# BpodFSM_2Plus_r1_3.net
KiCad netlist of a schematic drawn in EAGLE
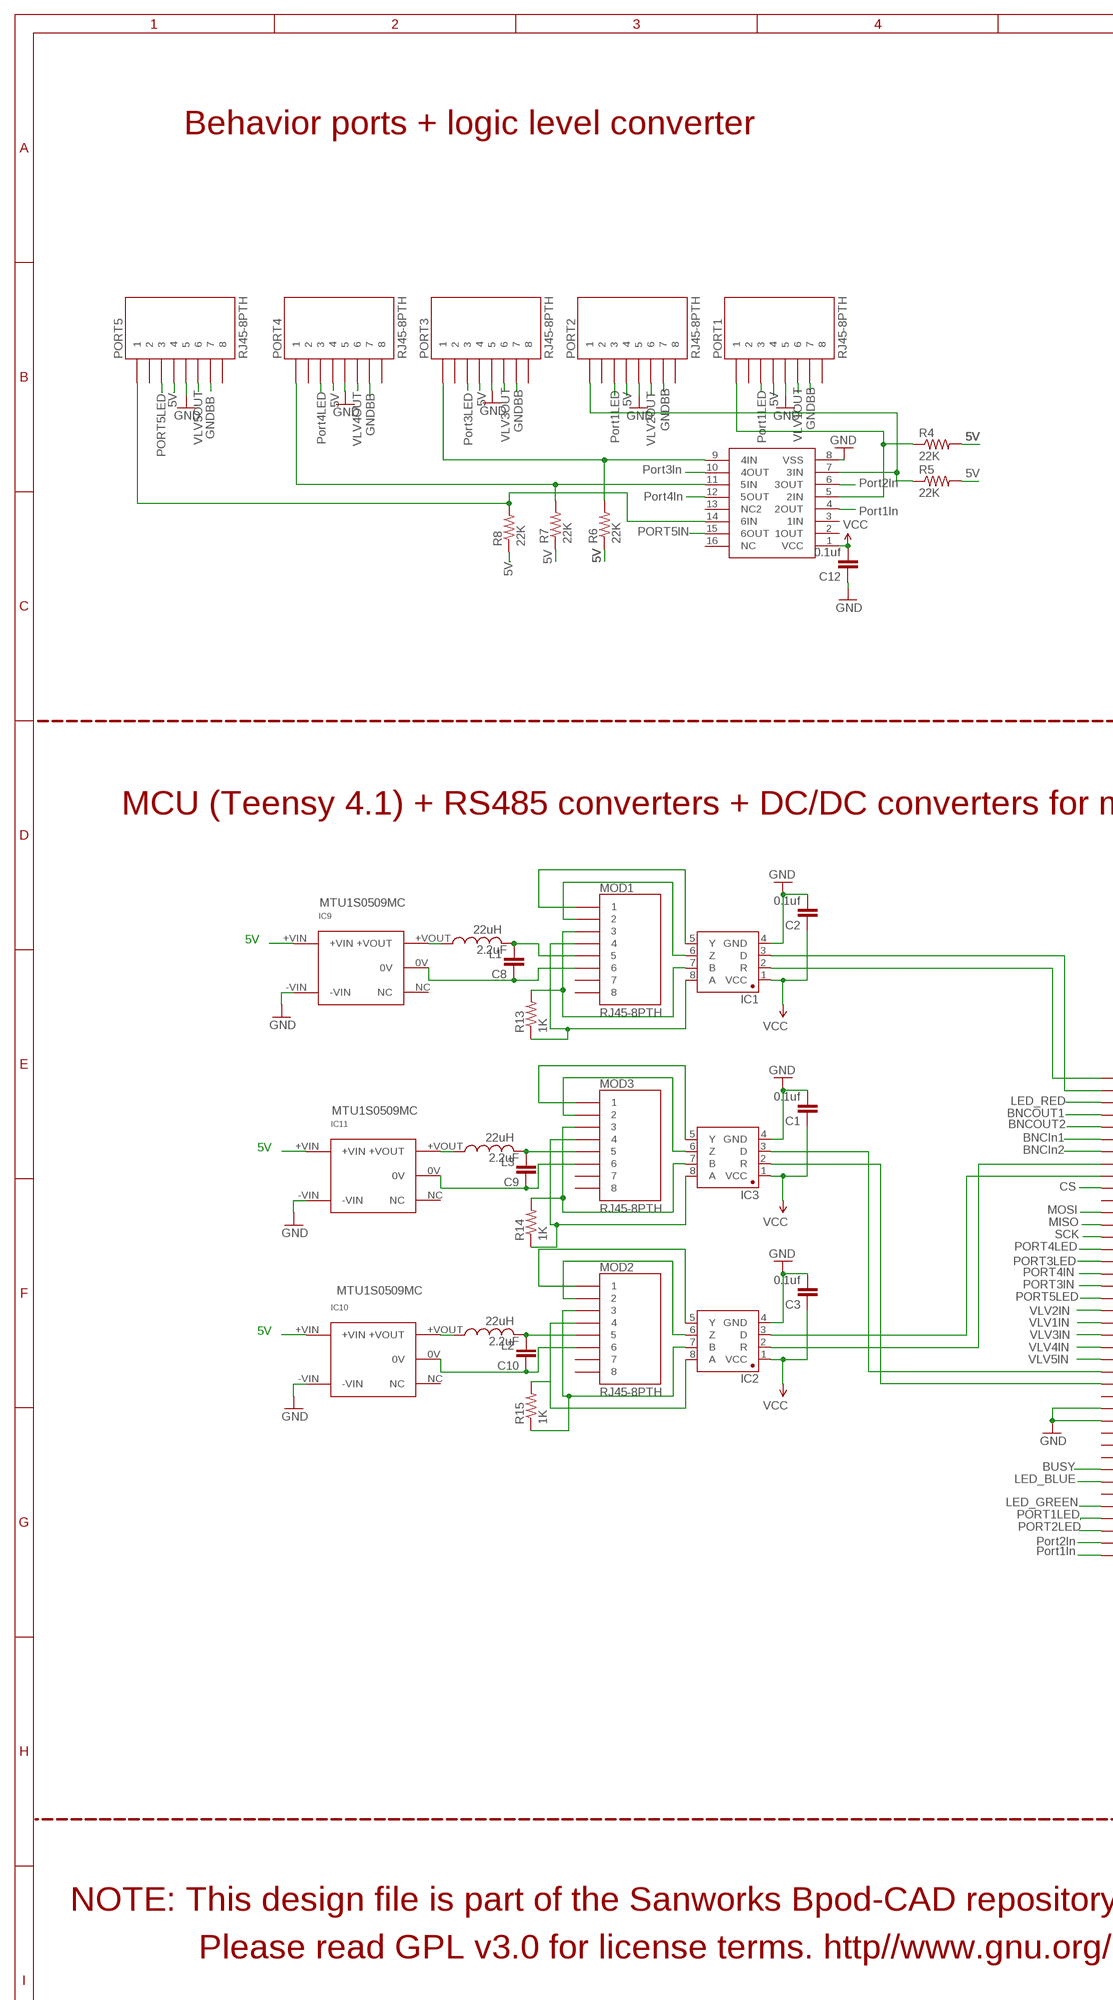
[diagram p0: schematic, sheet 1, part 1 of 2]
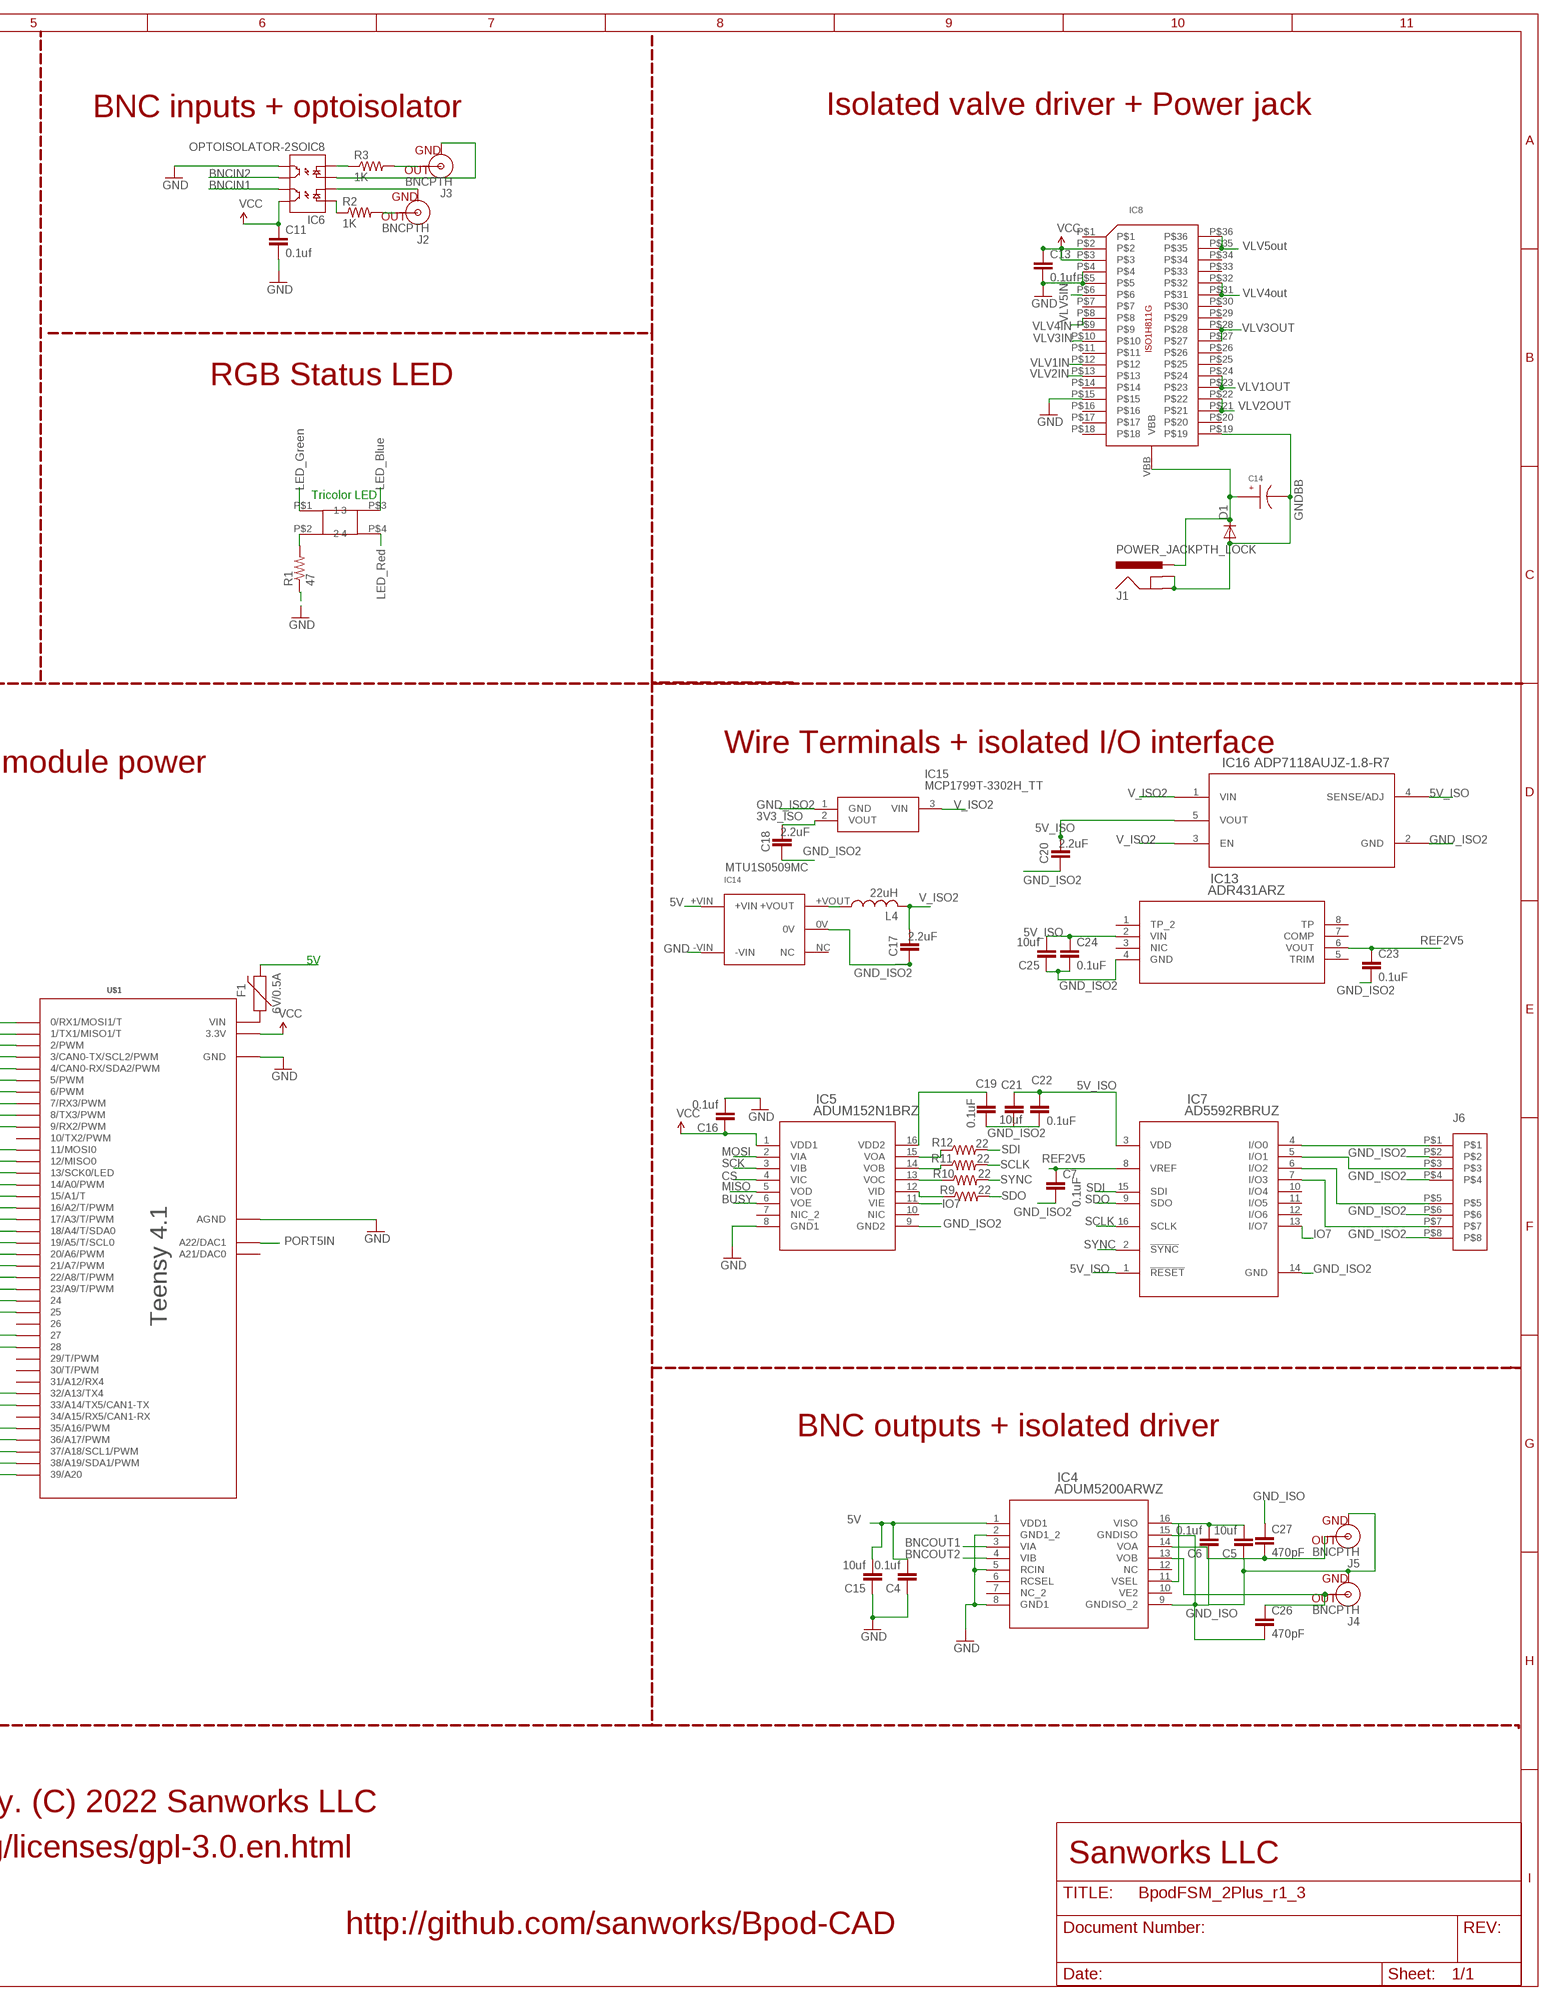
[diagram p1: schematic, sheet 1, part 2 of 2]

(export (version "E")
  (design (tool "Eeschema 10.0.6"))
  (components
    (comp (ref "C1")
      (value "0.1uf")
      (footprint "eagle-import:0805")
      (libsource (lib "eagle-import") (part "1.0UF-0805-25V-10%"))
    )
    (comp (ref "C2")
      (value "0.1uf")
      (footprint "eagle-import:0805")
      (libsource (lib "eagle-import") (part "1.0UF-0805-25V-10%"))
    )
    (comp (ref "C3")
      (value "0.1uf")
      (footprint "eagle-import:0805")
      (libsource (lib "eagle-import") (part "1.0UF-0805-25V-10%"))
    )
    (comp (ref "C4")
      (value "0.1uf")
      (footprint "eagle-import:0805")
      (libsource (lib "eagle-import") (part "1.0UF-0805-25V-10%"))
    )
    (comp (ref "C5")
      (value "10uf")
      (footprint "eagle-import:1206@1")
      (libsource (lib "eagle-import") (part "CAP1206"))
    )
    (comp (ref "C6")
      (value "0.1uf")
      (footprint "eagle-import:0805")
      (libsource (lib "eagle-import") (part "1.0UF-0805-25V-10%"))
    )
    (comp (ref "C7")
      (value "0.1uF")
      (footprint "eagle-import:0805")
      (libsource (lib "eagle-import") (part "1.0UF-0805-25V-10%"))
    )
    (comp (ref "C8")
      (value "2.2uF")
      (footprint "eagle-import:0805")
      (libsource (lib "eagle-import") (part "1.0UF-0805-25V-(+80/-20%)"))
    )
    (comp (ref "C9")
      (value "2.2uF")
      (footprint "eagle-import:0805")
      (libsource (lib "eagle-import") (part "1.0UF-0805-25V-(+80/-20%)"))
    )
    (comp (ref "C10")
      (value "2.2uF")
      (footprint "eagle-import:0805")
      (libsource (lib "eagle-import") (part "1.0UF-0805-25V-(+80/-20%)"))
    )
    (comp (ref "C11")
      (value "0.1uf")
      (footprint "eagle-import:0805")
      (libsource (lib "eagle-import") (part "1.0UF-0805-25V-10%"))
    )
    (comp (ref "C12")
      (value "0.1uf")
      (footprint "eagle-import:0805")
      (libsource (lib "eagle-import") (part "1.0UF-0805-25V-10%"))
    )
    (comp (ref "C13")
      (value "0.1uf")
      (footprint "eagle-import:0805")
      (libsource (lib "eagle-import") (part "1.0UF-0805-25V-10%"))
    )
    (comp (ref "C14")
      (value "EEE-FK1H100UR")
      (footprint "eagle-import:EEE-FK1H100UR")
      (libsource (lib "eagle-import") (part "EEE-FK1H100UR"))
    )
    (comp (ref "C15")
      (value "10uf")
      (footprint "eagle-import:1206@1")
      (libsource (lib "eagle-import") (part "CAP1206"))
    )
    (comp (ref "C16")
      (value "0.1uf")
      (footprint "eagle-import:0805")
      (libsource (lib "eagle-import") (part "1.0UF-0805-25V-10%"))
    )
    (comp (ref "C17")
      (value "2.2uF")
      (footprint "eagle-import:0805")
      (libsource (lib "eagle-import") (part "1.0UF-0805-25V-(+80/-20%)"))
    )
    (comp (ref "C18")
      (value "2.2uF")
      (footprint "eagle-import:0805")
      (libsource (lib "eagle-import") (part "1.0UF-0805-25V-(+80/-20%)"))
    )
    (comp (ref "C19")
      (value "0.1uF")
      (footprint "eagle-import:0805")
      (libsource (lib "eagle-import") (part "1.0UF-0805-25V-10%"))
    )
    (comp (ref "C20")
      (value "2.2uF")
      (footprint "eagle-import:0805")
      (libsource (lib "eagle-import") (part "1.0UF-0805-25V-(+80/-20%)"))
    )
    (comp (ref "C21")
      (value "10uf")
      (footprint "eagle-import:1206@1")
      (libsource (lib "eagle-import") (part "CAP1206"))
    )
    (comp (ref "C22")
      (value "0.1uF")
      (footprint "eagle-import:0805")
      (libsource (lib "eagle-import") (part "1.0UF-0805-25V-10%"))
    )
    (comp (ref "C23")
      (value "0.1uF")
      (footprint "eagle-import:0805")
      (libsource (lib "eagle-import") (part "1.0UF-0805-25V-10%"))
    )
    (comp (ref "C24")
      (value "0.1uF")
      (footprint "eagle-import:0805")
      (libsource (lib "eagle-import") (part "1.0UF-0805-25V-10%"))
    )
    (comp (ref "C25")
      (value "10uf")
      (footprint "eagle-import:1206@1")
      (libsource (lib "eagle-import") (part "CAP1206"))
    )
    (comp (ref "C26")
      (value "470pF")
      (footprint "eagle-import:0805")
      (libsource (lib "eagle-import") (part "1.0UF-0805-25V-10%"))
    )
    (comp (ref "C27")
      (value "470pF")
      (footprint "eagle-import:0805")
      (libsource (lib "eagle-import") (part "1.0UF-0805-25V-10%"))
    )
    (comp (ref "D1")
      (value "DIODE-DO214AA")
      (footprint "eagle-import:DO214AA")
      (libsource (lib "eagle-import") (part "DIODE-DO214AA"))
    )
    (comp (ref "F1")
      (value "6V/0.5A")
      (footprint "eagle-import:1206")
      (libsource (lib "eagle-import") (part "PPTC_HALF-AMP"))
    )
    (comp (ref "IC1")
      (value "SN65HVD31DR")
      (footprint "eagle-import:SO08")
      (libsource (lib "eagle-import") (part "SN65HVD31DR"))
    )
    (comp (ref "IC2")
      (value "SN65HVD31DR")
      (footprint "eagle-import:SO08")
      (libsource (lib "eagle-import") (part "SN65HVD31DR"))
    )
    (comp (ref "IC3")
      (value "SN65HVD31DR")
      (footprint "eagle-import:SO08")
      (libsource (lib "eagle-import") (part "SN65HVD31DR"))
    )
    (comp (ref "IC4")
      (value "ADUM5200ARWZ")
      (footprint "eagle-import:RW_16")
      (libsource (lib "eagle-import") (part "ADUM5200ARWZ"))
    )
    (comp (ref "IC5")
      (value "ADUM152N1BRZ")
      (footprint "eagle-import:R-16_ADI")
      (fields (field (name "COPYRIGHT") "Copyright (C) 2018 Accelerated Designs. All rights reserved"))
      (libsource (lib "eagle-import") (part "ADUM152N1BRZ"))
    )
    (comp (ref "IC6")
      (value "OPTOISOLATOR-2SOIC8")
      (footprint "eagle-import:SO08-2")
      (libsource (lib "eagle-import") (part "OPTOISOLATOR-2SOIC8"))
    )
    (comp (ref "IC7")
      (value "AD5592RBRUZ")
      (footprint "eagle-import:RU_16_ADI")
      (libsource (lib "eagle-import") (part "AD5592RBRUZ"))
    )
    (comp (ref "IC8")
      (value "ISO1H811G")
      (footprint "eagle-import:ISO1H811G")
      (libsource (lib "eagle-import") (part "ISO1H811G"))
    )
    (comp (ref "IC9")
      (value "9V")
      (footprint "eagle-import:MTU1D0505MC")
      (libsource (lib "eagle-import") (part "MTU1D0505MC"))
    )
    (comp (ref "IC10")
      (value "9V")
      (footprint "eagle-import:MTU1D0505MC")
      (libsource (lib "eagle-import") (part "MTU1D0505MC"))
    )
    (comp (ref "IC11")
      (value "9V")
      (footprint "eagle-import:MTU1D0505MC")
      (libsource (lib "eagle-import") (part "MTU1D0505MC"))
    )
    (comp (ref "IC12")
      (value "CD4050")
      (footprint "eagle-import:SO16")
      (libsource (lib "eagle-import") (part "CD4050"))
    )
    (comp (ref "IC13")
      (value "ADR431ARZ")
      (footprint "eagle-import:R_8_ADI")
      (libsource (lib "eagle-import") (part "ADR431ARZ"))
    )
    (comp (ref "IC14")
      (value "5V")
      (footprint "eagle-import:MTU1D0505MC")
      (libsource (lib "eagle-import") (part "MTU1D0505MC"))
    )
    (comp (ref "IC15")
      (value "MCP1799T-3302H_TT")
      (footprint "eagle-import:SOT95P237X112-3N")
      (fields
        (field (name "MANUFACTURER_PART_NUMBER") "MCP1799T-3302H/TT")
        (field (name "MOUSER_PART_NUMBER") "579-CP1799T-3302H/TT")
      )
      (libsource (lib "eagle-import") (part "MCP1799T-3302H_TT"))
    )
    (comp (ref "IC16")
      (value "ADP7118AUJZ-1.8-R7")
      (footprint "eagle-import:UJ_5")
      (libsource (lib "eagle-import") (part "ADP7118AUJZ-1.8-R7"))
    )
    (comp (ref "J1")
      (value "POWER_JACKPTH_LOCK")
      (footprint "eagle-import:POWER_JACK_PTH_LOCK")
      (libsource (lib "eagle-import") (part "POWER_JACKPTH_LOCK"))
    )
    (comp (ref "J2")
      (value "BNCPTH")
      (footprint "eagle-import:BNC")
      (libsource (lib "eagle-import") (part "BNCPTH"))
    )
    (comp (ref "J3")
      (value "BNCPTH")
      (footprint "eagle-import:BNC")
      (libsource (lib "eagle-import") (part "BNCPTH"))
    )
    (comp (ref "J4")
      (value "BNCPTH")
      (footprint "eagle-import:BNC")
      (libsource (lib "eagle-import") (part "BNCPTH"))
    )
    (comp (ref "J5")
      (value "BNCPTH")
      (footprint "eagle-import:BNC")
      (libsource (lib "eagle-import") (part "BNCPTH"))
    )
    (comp (ref "J6")
      (value "8POS_MOLEX_SOCKET")
      (footprint "eagle-import:8POS_MOLEX_SOCKET")
      (libsource (lib "eagle-import") (part "8POS_MOLEX_SOCKET"))
    )
    (comp (ref "L1")
      (value "22uH")
      (footprint "eagle-import:L3225M")
      (libsource (lib "eagle-import") (part "L-USL3225M"))
    )
    (comp (ref "L2")
      (value "22uH")
      (footprint "eagle-import:L3225M")
      (libsource (lib "eagle-import") (part "L-USL3225M"))
    )
    (comp (ref "L3")
      (value "22uH")
      (footprint "eagle-import:L3225M")
      (libsource (lib "eagle-import") (part "L-USL3225M"))
    )
    (comp (ref "L4")
      (value "22uH")
      (footprint "eagle-import:L3225M")
      (libsource (lib "eagle-import") (part "L-USL3225M"))
    )
    (comp (ref "MOD1")
      (value "RJ45-8PTH")
      (footprint "eagle-import:RJ45-8")
      (libsource (lib "eagle-import") (part "RJ45-8PTH"))
    )
    (comp (ref "MOD2")
      (value "RJ45-8PTH")
      (footprint "eagle-import:RJ45-8")
      (libsource (lib "eagle-import") (part "RJ45-8PTH"))
    )
    (comp (ref "MOD3")
      (value "RJ45-8PTH")
      (footprint "eagle-import:RJ45-8")
      (libsource (lib "eagle-import") (part "RJ45-8PTH"))
    )
    (comp (ref "PORT1")
      (value "RJ45-8PTH")
      (footprint "eagle-import:RJ45-8")
      (libsource (lib "eagle-import") (part "RJ45-8PTH"))
    )
    (comp (ref "PORT2")
      (value "RJ45-8PTH")
      (footprint "eagle-import:RJ45-8")
      (libsource (lib "eagle-import") (part "RJ45-8PTH"))
    )
    (comp (ref "PORT3")
      (value "RJ45-8PTH")
      (footprint "eagle-import:RJ45-8")
      (libsource (lib "eagle-import") (part "RJ45-8PTH"))
    )
    (comp (ref "PORT4")
      (value "RJ45-8PTH")
      (footprint "eagle-import:RJ45-8")
      (libsource (lib "eagle-import") (part "RJ45-8PTH"))
    )
    (comp (ref "PORT5")
      (value "RJ45-8PTH")
      (footprint "eagle-import:RJ45-8")
      (libsource (lib "eagle-import") (part "RJ45-8PTH"))
    )
    (comp (ref "R1")
      (value "47")
      (footprint "eagle-import:1206")
      (libsource (lib "eagle-import") (part "RESISTOR1206"))
    )
    (comp (ref "R2")
      (value "1K")
      (footprint "eagle-import:1206")
      (libsource (lib "eagle-import") (part "SparkFun-Resistors_RESISTOR1206"))
    )
    (comp (ref "R3")
      (value "1K")
      (footprint "eagle-import:1206")
      (libsource (lib "eagle-import") (part "SparkFun-Resistors_RESISTOR1206"))
    )
    (comp (ref "R4")
      (value "22K")
      (footprint "eagle-import:1206")
      (libsource (lib "eagle-import") (part "SparkFun-Resistors_RESISTOR1206"))
    )
    (comp (ref "R5")
      (value "22K")
      (footprint "eagle-import:1206")
      (libsource (lib "eagle-import") (part "SparkFun-Resistors_RESISTOR1206"))
    )
    (comp (ref "R6")
      (value "22K")
      (footprint "eagle-import:1206")
      (libsource (lib "eagle-import") (part "SparkFun-Resistors_RESISTOR1206"))
    )
    (comp (ref "R7")
      (value "22K")
      (footprint "eagle-import:1206")
      (libsource (lib "eagle-import") (part "SparkFun-Resistors_RESISTOR1206"))
    )
    (comp (ref "R8")
      (value "22K")
      (footprint "eagle-import:1206")
      (libsource (lib "eagle-import") (part "SparkFun-Resistors_RESISTOR1206"))
    )
    (comp (ref "R9")
      (value "22")
      (footprint "eagle-import:R0805")
      (libsource (lib "eagle-import") (part "R-US_R0805"))
    )
    (comp (ref "R10")
      (value "22")
      (footprint "eagle-import:R0805")
      (libsource (lib "eagle-import") (part "R-US_R0805"))
    )
    (comp (ref "R11")
      (value "22")
      (footprint "eagle-import:R0805")
      (libsource (lib "eagle-import") (part "R-US_R0805"))
    )
    (comp (ref "R12")
      (value "22")
      (footprint "eagle-import:R0805")
      (libsource (lib "eagle-import") (part "R-US_R0805"))
    )
    (comp (ref "R13")
      (value "1K")
      (footprint "eagle-import:1206")
      (libsource (lib "eagle-import") (part "SparkFun-Resistors_RESISTOR1206"))
    )
    (comp (ref "R14")
      (value "1K")
      (footprint "eagle-import:1206")
      (libsource (lib "eagle-import") (part "SparkFun-Resistors_RESISTOR1206"))
    )
    (comp (ref "R15")
      (value "1K")
      (footprint "eagle-import:1206")
      (libsource (lib "eagle-import") (part "SparkFun-Resistors_RESISTOR1206"))
    )
    (comp (ref "U$1")
      (value "TEENSY_3.6_DIL")
      (footprint "eagle-import:TEENSY_3.6_DIL")
      (libsource (lib "eagle-import") (part "TEENSY_3.6_DIL"))
    )
    (comp (ref "U$8")
      (value "SQUARE_TRICOLOR_LED")
      (footprint "eagle-import:SQUARE_TRICOLOR_LED")
      (libsource (lib "eagle-import") (part "SQUARE_TRICOLOR_LED"))
    )
  )
  (nets
    (net (code "1") (name "/3V3_ISO") (class "Default")
      (node (ref "C18") (pin "2") (pinfunction "2_2") (pintype "passive"))
      (node (ref "C19") (pin "1") (pinfunction "1_1") (pintype "passive"))
      (node (ref "IC15") (pin "2") (pinfunction "VOUT_2") (pintype "bidirectional"))
      (node (ref "IC5") (pin "16") (pinfunction "VDD2_16") (pintype "power_in"))
    )
    (net (code "2") (name "/5V") (class "Default")
      (node (ref "C15") (pin "2") (pinfunction "2_2") (pintype "passive"))
      (node (ref "C4") (pin "2") (pinfunction "2_2") (pintype "passive"))
      (node (ref "F1") (pin "2") (pinfunction "2_2") (pintype "bidirectional"))
      (node (ref "IC10") (pin "+VIN") (pinfunction "+VIN_+VIN") (pintype "bidirectional"))
      (node (ref "IC11") (pin "+VIN") (pinfunction "+VIN_+VIN") (pintype "bidirectional"))
      (node (ref "IC14") (pin "+VIN") (pinfunction "+VIN_+VIN") (pintype "bidirectional"))
      (node (ref "IC4") (pin "1") (pinfunction "VDD1_1") (pintype "passive"))
      (node (ref "IC9") (pin "+VIN") (pinfunction "+VIN_+VIN") (pintype "bidirectional"))
      (node (ref "PORT1") (pin "4") (pinfunction "4_4") (pintype "bidirectional"))
      (node (ref "PORT2") (pin "4") (pinfunction "4_4") (pintype "bidirectional"))
      (node (ref "PORT3") (pin "4") (pinfunction "4_4") (pintype "bidirectional"))
      (node (ref "PORT4") (pin "4") (pinfunction "4_4") (pintype "bidirectional"))
      (node (ref "PORT5") (pin "4") (pinfunction "4_4") (pintype "bidirectional"))
      (node (ref "R4") (pin "2") (pinfunction "2_2") (pintype "passive"))
      (node (ref "R5") (pin "2") (pinfunction "2_2") (pintype "passive"))
      (node (ref "R6") (pin "1") (pinfunction "1_1") (pintype "passive"))
      (node (ref "R7") (pin "1") (pinfunction "1_1") (pintype "passive"))
      (node (ref "R8") (pin "1") (pinfunction "1_1") (pintype "passive"))
    )
    (net (code "3") (name "/5V_ISO") (class "Default")
      (node (ref "C20") (pin "2") (pinfunction "2_2") (pintype "passive"))
      (node (ref "C21") (pin "2") (pinfunction "2_2") (pintype "passive"))
      (node (ref "C22") (pin "1") (pinfunction "1_1") (pintype "passive"))
      (node (ref "C24") (pin "1") (pinfunction "1_1") (pintype "passive"))
      (node (ref "C25") (pin "2") (pinfunction "2_2") (pintype "passive"))
      (node (ref "IC13") (pin "2") (pinfunction "VIN_2") (pintype "input"))
      (node (ref "IC16") (pin "4") (pinfunction "SENSE/ADJ_4") (pintype "passive"))
      (node (ref "IC16") (pin "5") (pinfunction "VOUT_5") (pintype "passive"))
      (node (ref "IC7") (pin "1") (pinfunction "~{RESET}_1") (pintype "passive"))
      (node (ref "IC7") (pin "3") (pinfunction "VDD_3") (pintype "passive"))
    )
    (net (code "4") (name "/BNCIN1") (class "Default")
      (node (ref "IC6") (pin "7") (pinfunction "EM1_7") (pintype "bidirectional"))
      (node (ref "U$1") (pin "6") (pinfunction "6/PWM_6") (pintype "bidirectional"))
    )
    (net (code "5") (name "/BNCIN2") (class "Default")
      (node (ref "IC6") (pin "6") (pinfunction "CL2_6") (pintype "bidirectional"))
      (node (ref "U$1") (pin "5") (pinfunction "5/PWM_5") (pintype "bidirectional"))
    )
    (net (code "6") (name "/BNCOUT1") (class "Default")
      (node (ref "IC4") (pin "3") (pinfunction "VIA_3") (pintype "passive"))
      (node (ref "U$1") (pin "3") (pinfunction "3/CAN0-TX/SCL2/PWM_3") (pintype "bidirectional"))
    )
    (net (code "7") (name "/BNCOUT2") (class "Default")
      (node (ref "IC4") (pin "4") (pinfunction "VIB_4") (pintype "passive"))
      (node (ref "U$1") (pin "4") (pinfunction "4/CAN0-RX/SDA2/PWM_4") (pintype "bidirectional"))
    )
    (net (code "8") (name "/BUSY") (class "Default")
      (node (ref "IC5") (pin "6") (pinfunction "VOE_6") (pintype "output"))
      (node (ref "U$1") (pin "32/A13") (pinfunction "32/A13/TX4_32/A13") (pintype "bidirectional"))
    )
    (net (code "9") (name "/CS") (class "Default")
      (node (ref "IC5") (pin "4") (pinfunction "VIC_4") (pintype "input"))
      (node (ref "U$1") (pin "9") (pinfunction "9/RX2/PWM_9") (pintype "bidirectional"))
    )
    (net (code "10") (name "/GNDBB") (class "Default")
      (node (ref "C14") (pin "CATHODE") (pinfunction "CATHODE_CATHODE") (pintype "bidirectional"))
      (node (ref "D1") (pin "A") (pinfunction "A_A") (pintype "passive"))
      (node (ref "IC8") (pin "P$19") (pinfunction "P$19_P$19") (pintype "bidirectional"))
      (node (ref "J1") (pin "GND") (pinfunction "GND_GND") (pintype "bidirectional"))
      (node (ref "J1") (pin "GNDBREAK") (pinfunction "GNDBREAK_GNDBREAK") (pintype "bidirectional"))
      (node (ref "PORT1") (pin "7") (pinfunction "7_7") (pintype "bidirectional"))
      (node (ref "PORT2") (pin "7") (pinfunction "7_7") (pintype "bidirectional"))
      (node (ref "PORT3") (pin "7") (pinfunction "7_7") (pintype "bidirectional"))
      (node (ref "PORT4") (pin "7") (pinfunction "7_7") (pintype "bidirectional"))
      (node (ref "PORT5") (pin "7") (pinfunction "7_7") (pintype "bidirectional"))
    )
    (net (code "11") (name "/GND_ISO") (class "Default")
      (node (ref "C26") (pin "2") (pinfunction "2_2") (pintype "passive"))
      (node (ref "C27") (pin "1") (pinfunction "1_1") (pintype "passive"))
      (node (ref "C5") (pin "1") (pinfunction "1_1") (pintype "passive"))
      (node (ref "C6") (pin "1") (pinfunction "1_1") (pintype "passive"))
      (node (ref "IC4") (pin "15") (pinfunction "GNDISO_15") (pintype "passive"))
      (node (ref "IC4") (pin "9") (pinfunction "GNDISO_2_9") (pintype "passive"))
      (node (ref "J4") (pin "GND") (pinfunction "GND_GND") (pintype "bidirectional"))
      (node (ref "J5") (pin "GND") (pinfunction "GND_GND") (pintype "bidirectional"))
    )
    (net (code "12") (name "/GND_ISO2") (class "Default")
      (node (ref "C17") (pin "1") (pinfunction "1_1") (pintype "passive"))
      (node (ref "C18") (pin "1") (pinfunction "1_1") (pintype "passive"))
      (node (ref "C19") (pin "2") (pinfunction "2_2") (pintype "passive"))
      (node (ref "C20") (pin "1") (pinfunction "1_1") (pintype "passive"))
      (node (ref "C21") (pin "1") (pinfunction "1_1") (pintype "passive"))
      (node (ref "C22") (pin "2") (pinfunction "2_2") (pintype "passive"))
      (node (ref "C23") (pin "2") (pinfunction "2_2") (pintype "passive"))
      (node (ref "C24") (pin "2") (pinfunction "2_2") (pintype "passive"))
      (node (ref "C25") (pin "1") (pinfunction "1_1") (pintype "passive"))
      (node (ref "C7") (pin "2") (pinfunction "2_2") (pintype "passive"))
      (node (ref "IC13") (pin "4") (pinfunction "GND_4") (pintype "power_in"))
      (node (ref "IC14") (pin "0V") (pinfunction "0V_0V") (pintype "bidirectional"))
      (node (ref "IC15") (pin "1") (pinfunction "GND_1") (pintype "bidirectional"))
      (node (ref "IC16") (pin "2") (pinfunction "GND_2") (pintype "passive"))
      (node (ref "IC5") (pin "9") (pinfunction "GND2_9") (pintype "passive"))
      (node (ref "IC7") (pin "14") (pinfunction "GND_14") (pintype "passive"))
      (node (ref "J6") (pin "P$2") (pinfunction "P$2_P$2") (pintype "bidirectional"))
      (node (ref "J6") (pin "P$4") (pinfunction "P$4_P$4") (pintype "bidirectional"))
      (node (ref "J6") (pin "P$6") (pinfunction "P$6_P$6") (pintype "bidirectional"))
      (node (ref "J6") (pin "P$8") (pinfunction "P$8_P$8") (pintype "bidirectional"))
    )
    (net (code "13") (name "/IO7") (class "Default")
      (node (ref "IC5") (pin "11") (pinfunction "VIE_11") (pintype "input"))
      (node (ref "IC7") (pin "13") (pinfunction "I/O7_13") (pintype "passive"))
    )
    (net (code "14") (name "/LED_BLUE") (class "Default")
      (node (ref "U$1") (pin "33/A14") (pinfunction "33/A14/TX5/CAN1-TX_33/A14") (pintype "bidirectional"))
      (node (ref "U$8") (pin "P$3") (pinfunction "3_P$3") (pintype "bidirectional"))
    )
    (net (code "15") (name "/LED_GREEN") (class "Default")
      (node (ref "U$1") (pin "35/A16") (pinfunction "35/A16/PWM_35/A16") (pintype "bidirectional"))
      (node (ref "U$8") (pin "P$1") (pinfunction "1_P$1") (pintype "bidirectional"))
    )
    (net (code "16") (name "/LED_RED") (class "Default")
      (node (ref "U$1") (pin "2") (pinfunction "2/PWM_2") (pintype "bidirectional"))
      (node (ref "U$8") (pin "P$4") (pinfunction "4_P$4") (pintype "bidirectional"))
    )
    (net (code "17") (name "/MISO") (class "Default")
      (node (ref "IC5") (pin "5") (pinfunction "VOD_5") (pintype "output"))
      (node (ref "U$1") (pin "12") (pinfunction "12/MISO0_12") (pintype "bidirectional"))
    )
    (net (code "18") (name "/MOSI") (class "Default")
      (node (ref "IC5") (pin "2") (pinfunction "VIA_2") (pintype "input"))
      (node (ref "U$1") (pin "11") (pinfunction "11/MOSI0_11") (pintype "bidirectional"))
    )
    (net (code "19") (name "/PORT1IN") (class "Default")
      (node (ref "IC12") (pin "4") (pinfunction "2OUT_4") (pintype "bidirectional"))
      (node (ref "U$1") (pin "39/A20") (pinfunction "39/A20_39/A20") (pintype "bidirectional"))
    )
    (net (code "20") (name "/PORT1LED") (class "Default")
      (node (ref "PORT1") (pin "3") (pinfunction "3_3") (pintype "bidirectional"))
      (node (ref "U$1") (pin "36/A17") (pinfunction "36/A17/PWM_36/A17") (pintype "bidirectional"))
    )
    (net (code "21") (name "/PORT2IN") (class "Default")
      (node (ref "IC12") (pin "6") (pinfunction "3OUT_6") (pintype "bidirectional"))
      (node (ref "U$1") (pin "38/A19") (pinfunction "38/A19/SDA1/PWM_38/A19") (pintype "bidirectional"))
    )
    (net (code "22") (name "/PORT2LED") (class "Default")
      (node (ref "PORT2") (pin "3") (pinfunction "3_3") (pintype "bidirectional"))
      (node (ref "U$1") (pin "37/A18") (pinfunction "37/A18/SCL1/PWM_37/A18") (pintype "bidirectional"))
    )
    (net (code "23") (name "/PORT3IN") (class "Default")
      (node (ref "IC12") (pin "10") (pinfunction "4OUT_10") (pintype "bidirectional"))
      (node (ref "U$1") (pin "17/A3") (pinfunction "17/A3/T/PWM_17/A3") (pintype "bidirectional"))
    )
    (net (code "24") (name "/PORT3LED") (class "Default")
      (node (ref "PORT3") (pin "3") (pinfunction "3_3") (pintype "bidirectional"))
      (node (ref "U$1") (pin "15/A1") (pinfunction "15/A1/T_15/A1") (pintype "bidirectional"))
    )
    (net (code "25") (name "/PORT4IN") (class "Default")
      (node (ref "IC12") (pin "12") (pinfunction "5OUT_12") (pintype "bidirectional"))
      (node (ref "U$1") (pin "16/A2") (pinfunction "16/A2/T/PWM_16/A2") (pintype "bidirectional"))
    )
    (net (code "26") (name "/PORT4LED") (class "Default")
      (node (ref "PORT4") (pin "3") (pinfunction "3_3") (pintype "bidirectional"))
      (node (ref "U$1") (pin "14/A0") (pinfunction "14/A0/PWM_14/A0") (pintype "bidirectional"))
    )
    (net (code "27") (name "/PORT5IN") (class "Default")
      (node (ref "IC12") (pin "15") (pinfunction "6OUT_15") (pintype "bidirectional"))
      (node (ref "U$1") (pin "A22") (pinfunction "A22/DAC1_A22") (pintype "bidirectional"))
    )
    (net (code "28") (name "/PORT5LED") (class "Default")
      (node (ref "PORT5") (pin "3") (pinfunction "3_3") (pintype "bidirectional"))
      (node (ref "U$1") (pin "18/A4") (pinfunction "18/A4/T/SDA0_18/A4") (pintype "bidirectional"))
    )
    (net (code "29") (name "/REF2V5") (class "Default")
      (node (ref "C23") (pin "1") (pinfunction "1_1") (pintype "passive"))
      (node (ref "C7") (pin "1") (pinfunction "1_1") (pintype "passive"))
      (node (ref "IC13") (pin "6") (pinfunction "VOUT_6") (pintype "output"))
      (node (ref "IC7") (pin "8") (pinfunction "VREF_8") (pintype "passive"))
    )
    (net (code "30") (name "/SCK") (class "Default")
      (node (ref "IC5") (pin "3") (pinfunction "VIB_3") (pintype "input"))
      (node (ref "U$1") (pin "13") (pinfunction "13/SCK0/LED_13") (pintype "bidirectional"))
    )
    (net (code "31") (name "/SCLK") (class "Default")
      (node (ref "IC7") (pin "16") (pinfunction "SCLK_16") (pintype "passive"))
      (node (ref "R11") (pin "2") (pinfunction "2_2") (pintype "passive"))
    )
    (net (code "32") (name "/SDI") (class "Default")
      (node (ref "IC7") (pin "15") (pinfunction "SDI_15") (pintype "passive"))
      (node (ref "R12") (pin "2") (pinfunction "2_2") (pintype "passive"))
    )
    (net (code "33") (name "/SDO") (class "Default")
      (node (ref "IC7") (pin "9") (pinfunction "SDO_9") (pintype "passive"))
      (node (ref "R9") (pin "2") (pinfunction "2_2") (pintype "passive"))
    )
    (net (code "34") (name "/SYNC") (class "Default")
      (node (ref "IC7") (pin "2") (pinfunction "~{SYNC}_2") (pintype "passive"))
      (node (ref "R10") (pin "2") (pinfunction "2_2") (pintype "passive"))
    )
    (net (code "35") (name "/VLV1IN") (class "Default")
      (node (ref "IC8") (pin "P$12") (pinfunction "P$12_P$12") (pintype "bidirectional"))
      (node (ref "U$1") (pin "20/A6") (pinfunction "20/A6/PWM_20/A6") (pintype "bidirectional"))
    )
    (net (code "36") (name "/VLV1OUT") (class "Default")
      (node (ref "IC8") (pin "P$23") (pinfunction "P$23_P$23") (pintype "bidirectional"))
      (node (ref "IC8") (pin "P$24") (pinfunction "P$24_P$24") (pintype "bidirectional"))
      (node (ref "PORT1") (pin "6") (pinfunction "6_6") (pintype "bidirectional"))
    )
    (net (code "37") (name "/VLV2IN") (class "Default")
      (node (ref "IC8") (pin "P$13") (pinfunction "P$13_P$13") (pintype "bidirectional"))
      (node (ref "U$1") (pin "19/A5") (pinfunction "19/A5/T/SCL0_19/A5") (pintype "bidirectional"))
    )
    (net (code "38") (name "/VLV2OUT") (class "Default")
      (node (ref "IC8") (pin "P$21") (pinfunction "P$21_P$21") (pintype "bidirectional"))
      (node (ref "IC8") (pin "P$22") (pinfunction "P$22_P$22") (pintype "bidirectional"))
      (node (ref "PORT2") (pin "6") (pinfunction "6_6") (pintype "bidirectional"))
    )
    (net (code "39") (name "/VLV3IN") (class "Default")
      (node (ref "IC8") (pin "P$10") (pinfunction "P$10_P$10") (pintype "bidirectional"))
      (node (ref "U$1") (pin "21/A7") (pinfunction "21/A7/PWM_21/A7") (pintype "bidirectional"))
    )
    (net (code "40") (name "/VLV3OUT") (class "Default")
      (node (ref "IC8") (pin "P$27") (pinfunction "P$27_P$27") (pintype "bidirectional"))
      (node (ref "IC8") (pin "P$28") (pinfunction "P$28_P$28") (pintype "bidirectional"))
      (node (ref "PORT3") (pin "6") (pinfunction "6_6") (pintype "bidirectional"))
    )
    (net (code "41") (name "/VLV4IN") (class "Default")
      (node (ref "IC8") (pin "P$8") (pinfunction "P$8_P$8") (pintype "bidirectional"))
      (node (ref "U$1") (pin "22/A8") (pinfunction "22/A8/T/PWM_22/A8") (pintype "bidirectional"))
    )
    (net (code "42") (name "/VLV4OUT") (class "Default")
      (node (ref "IC8") (pin "P$31") (pinfunction "P$31_P$31") (pintype "bidirectional"))
      (node (ref "IC8") (pin "P$32") (pinfunction "P$32_P$32") (pintype "bidirectional"))
      (node (ref "PORT4") (pin "6") (pinfunction "6_6") (pintype "bidirectional"))
    )
    (net (code "43") (name "/VLV5IN") (class "Default")
      (node (ref "IC8") (pin "P$6") (pinfunction "P$6_P$6") (pintype "bidirectional"))
      (node (ref "U$1") (pin "23/A9") (pinfunction "23/A9/T/PWM_23/A9") (pintype "bidirectional"))
    )
    (net (code "44") (name "/VLV5OUT") (class "Default")
      (node (ref "IC8") (pin "P$35") (pinfunction "P$35_P$35") (pintype "bidirectional"))
      (node (ref "IC8") (pin "P$36") (pinfunction "P$36_P$36") (pintype "bidirectional"))
      (node (ref "PORT5") (pin "6") (pinfunction "6_6") (pintype "bidirectional"))
    )
    (net (code "45") (name "/V_ISO2") (class "Default")
      (node (ref "C17") (pin "2") (pinfunction "2_2") (pintype "passive"))
      (node (ref "IC15") (pin "3") (pinfunction "VIN_3") (pintype "bidirectional"))
      (node (ref "IC16") (pin "1") (pinfunction "VIN_1") (pintype "passive"))
      (node (ref "IC16") (pin "3") (pinfunction "EN_3") (pintype "passive"))
      (node (ref "L4") (pin "2") (pinfunction "2_2") (pintype "passive"))
    )
    (net (code "46") (name "GND") (class "Default")
      (node (ref "C1") (pin "2") (pinfunction "2_2") (pintype "passive"))
      (node (ref "C11") (pin "2") (pinfunction "2_2") (pintype "passive"))
      (node (ref "C12") (pin "1") (pinfunction "1_1") (pintype "passive"))
      (node (ref "C13") (pin "2") (pinfunction "2_2") (pintype "passive"))
      (node (ref "C15") (pin "1") (pinfunction "1_1") (pintype "passive"))
      (node (ref "C16") (pin "2") (pinfunction "2_2") (pintype "passive"))
      (node (ref "C2") (pin "2") (pinfunction "2_2") (pintype "passive"))
      (node (ref "C3") (pin "2") (pinfunction "2_2") (pintype "passive"))
      (node (ref "C4") (pin "1") (pinfunction "1_1") (pintype "passive"))
      (node (ref "IC1") (pin "4") (pinfunction "GND_4") (pintype "bidirectional"))
      (node (ref "IC10") (pin "-VIN") (pinfunction "-VIN_-VIN") (pintype "bidirectional"))
      (node (ref "IC11") (pin "-VIN") (pinfunction "-VIN_-VIN") (pintype "bidirectional"))
      (node (ref "IC12") (pin "8") (pinfunction "VSS_8") (pintype "bidirectional"))
      (node (ref "IC14") (pin "-VIN") (pinfunction "-VIN_-VIN") (pintype "bidirectional"))
      (node (ref "IC2") (pin "4") (pinfunction "GND_4") (pintype "bidirectional"))
      (node (ref "IC3") (pin "4") (pinfunction "GND_4") (pintype "bidirectional"))
      (node (ref "IC4") (pin "2") (pinfunction "GND1_2_2") (pintype "passive"))
      (node (ref "IC4") (pin "5") (pinfunction "RCIN_5") (pintype "passive"))
      (node (ref "IC4") (pin "8") (pinfunction "GND1_8") (pintype "passive"))
      (node (ref "IC5") (pin "8") (pinfunction "GND1_8") (pintype "passive"))
      (node (ref "IC6") (pin "5") (pinfunction "EM2_5") (pintype "bidirectional"))
      (node (ref "IC8") (pin "P$15") (pinfunction "P$15_P$15") (pintype "bidirectional"))
      (node (ref "IC8") (pin "P$4") (pinfunction "P$4_P$4") (pintype "bidirectional"))
      (node (ref "IC8") (pin "P$5") (pinfunction "P$5_P$5") (pintype "bidirectional"))
      (node (ref "IC9") (pin "-VIN") (pinfunction "-VIN_-VIN") (pintype "bidirectional"))
      (node (ref "PORT1") (pin "5") (pinfunction "5_5") (pintype "bidirectional"))
      (node (ref "PORT2") (pin "5") (pinfunction "5_5") (pintype "bidirectional"))
      (node (ref "PORT3") (pin "5") (pinfunction "5_5") (pintype "bidirectional"))
      (node (ref "PORT4") (pin "5") (pinfunction "5_5") (pintype "bidirectional"))
      (node (ref "PORT5") (pin "5") (pinfunction "5_5") (pintype "bidirectional"))
      (node (ref "R1") (pin "1") (pinfunction "1_1") (pintype "passive"))
      (node (ref "U$1") (pin "27") (pinfunction "27_27") (pintype "bidirectional"))
      (node (ref "U$1") (pin "28") (pinfunction "28_28") (pintype "bidirectional"))
      (node (ref "U$1") (pin "AGND") (pinfunction "AGND_AGND") (pintype "power_in"))
      (node (ref "U$1") (pin "GND") (pinfunction "GND_GND") (pintype "power_in"))
      (node (ref "U$1") (pin "GND1") (pinfunction "GND_GND1") (pintype "power_in"))
    )
    (net (code "47") (name "Net-(C8-Pad1)") (class "Default")
      (node (ref "C8") (pin "1") (pinfunction "1_1") (pintype "passive"))
      (node (ref "IC9") (pin "0V") (pinfunction "0V_0V") (pintype "bidirectional"))
      (node (ref "MOD1") (pin "6") (pinfunction "6_6") (pintype "bidirectional"))
    )
    (net (code "48") (name "Net-(C8-Pad2)") (class "Default")
      (node (ref "C8") (pin "2") (pinfunction "2_2") (pintype "passive"))
      (node (ref "L1") (pin "2") (pinfunction "2_2") (pintype "passive"))
      (node (ref "MOD1") (pin "5") (pinfunction "5_5") (pintype "bidirectional"))
    )
    (net (code "49") (name "Net-(C9-Pad1)") (class "Default")
      (node (ref "C9") (pin "1") (pinfunction "1_1") (pintype "passive"))
      (node (ref "IC11") (pin "0V") (pinfunction "0V_0V") (pintype "bidirectional"))
      (node (ref "MOD3") (pin "6") (pinfunction "6_6") (pintype "bidirectional"))
    )
    (net (code "50") (name "Net-(C9-Pad2)") (class "Default")
      (node (ref "C9") (pin "2") (pinfunction "2_2") (pintype "passive"))
      (node (ref "L3") (pin "2") (pinfunction "2_2") (pintype "passive"))
      (node (ref "MOD3") (pin "5") (pinfunction "5_5") (pintype "bidirectional"))
    )
    (net (code "51") (name "Net-(C10-Pad1)") (class "Default")
      (node (ref "C10") (pin "1") (pinfunction "1_1") (pintype "passive"))
      (node (ref "IC10") (pin "0V") (pinfunction "0V_0V") (pintype "bidirectional"))
      (node (ref "MOD2") (pin "6") (pinfunction "6_6") (pintype "bidirectional"))
    )
    (net (code "52") (name "Net-(C10-Pad2)") (class "Default")
      (node (ref "C10") (pin "2") (pinfunction "2_2") (pintype "passive"))
      (node (ref "L2") (pin "2") (pinfunction "2_2") (pintype "passive"))
      (node (ref "MOD2") (pin "5") (pinfunction "5_5") (pintype "bidirectional"))
    )
    (net (code "53") (name "Net-(C14-PadANODE)") (class "Default")
      (node (ref "C14") (pin "ANODE") (pinfunction "ANODE_ANODE") (pintype "bidirectional"))
      (node (ref "D1") (pin "C") (pinfunction "C_C") (pintype "passive"))
      (node (ref "IC8") (pin "VBB") (pinfunction "VBB_VBB") (pintype "bidirectional"))
      (node (ref "J1") (pin "PWR") (pinfunction "PWR_PWR") (pintype "bidirectional"))
    )
    (net (code "54") (name "Net-(F1-Pad1)") (class "Default")
      (node (ref "F1") (pin "1") (pinfunction "1_1") (pintype "bidirectional"))
      (node (ref "U$1") (pin "VIN") (pinfunction "VIN_VIN") (pintype "power_in"))
    )
    (net (code "55") (name "Net-(IC1-A)") (class "Default")
      (node (ref "IC1") (pin "8") (pinfunction "A_8") (pintype "bidirectional"))
      (node (ref "MOD1") (pin "4") (pinfunction "4_4") (pintype "bidirectional"))
      (node (ref "R13") (pin "1") (pinfunction "1_1") (pintype "passive"))
    )
    (net (code "56") (name "Net-(IC1-B)") (class "Default")
      (node (ref "IC1") (pin "7") (pinfunction "B_7") (pintype "bidirectional"))
      (node (ref "MOD1") (pin "3") (pinfunction "3_3") (pintype "bidirectional"))
      (node (ref "R13") (pin "2") (pinfunction "2_2") (pintype "passive"))
    )
    (net (code "57") (name "Net-(IC1-D)") (class "Default")
      (node (ref "IC1") (pin "3") (pinfunction "D_3") (pintype "bidirectional"))
      (node (ref "U$1") (pin "1") (pinfunction "1/TX1/MISO1/T_1") (pintype "bidirectional"))
    )
    (net (code "58") (name "Net-(IC1-R)") (class "Default")
      (node (ref "IC1") (pin "2") (pinfunction "R_2") (pintype "bidirectional"))
      (node (ref "U$1") (pin "0") (pinfunction "0/RX1/MOSI1/T_0") (pintype "bidirectional"))
    )
    (net (code "59") (name "Net-(IC1-Y)") (class "Default")
      (node (ref "IC1") (pin "5") (pinfunction "Y_5") (pintype "bidirectional"))
      (node (ref "MOD1") (pin "1") (pinfunction "1_1") (pintype "bidirectional"))
    )
    (net (code "60") (name "Net-(IC1-Z)") (class "Default")
      (node (ref "IC1") (pin "6") (pinfunction "Z_6") (pintype "bidirectional"))
      (node (ref "MOD1") (pin "2") (pinfunction "2_2") (pintype "bidirectional"))
    )
    (net (code "61") (name "Net-(IC2-A)") (class "Default")
      (node (ref "IC2") (pin "8") (pinfunction "A_8") (pintype "bidirectional"))
      (node (ref "MOD2") (pin "4") (pinfunction "4_4") (pintype "bidirectional"))
      (node (ref "R15") (pin "2") (pinfunction "2_2") (pintype "passive"))
    )
    (net (code "62") (name "Net-(IC2-B)") (class "Default")
      (node (ref "IC2") (pin "7") (pinfunction "B_7") (pintype "bidirectional"))
      (node (ref "MOD2") (pin "3") (pinfunction "3_3") (pintype "bidirectional"))
      (node (ref "R15") (pin "1") (pinfunction "1_1") (pintype "passive"))
    )
    (net (code "63") (name "Net-(IC2-D)") (class "Default")
      (node (ref "IC2") (pin "3") (pinfunction "D_3") (pintype "bidirectional"))
      (node (ref "U$1") (pin "8") (pinfunction "8/TX3/PWM_8") (pintype "bidirectional"))
    )
    (net (code "64") (name "Net-(IC2-R)") (class "Default")
      (node (ref "IC2") (pin "2") (pinfunction "R_2") (pintype "bidirectional"))
      (node (ref "U$1") (pin "7") (pinfunction "7/RX3/PWM_7") (pintype "bidirectional"))
    )
    (net (code "65") (name "Net-(IC2-Y)") (class "Default")
      (node (ref "IC2") (pin "5") (pinfunction "Y_5") (pintype "bidirectional"))
      (node (ref "MOD2") (pin "1") (pinfunction "1_1") (pintype "bidirectional"))
    )
    (net (code "66") (name "Net-(IC2-Z)") (class "Default")
      (node (ref "IC2") (pin "6") (pinfunction "Z_6") (pintype "bidirectional"))
      (node (ref "MOD2") (pin "2") (pinfunction "2_2") (pintype "bidirectional"))
    )
    (net (code "67") (name "Net-(IC3-A)") (class "Default")
      (node (ref "IC3") (pin "8") (pinfunction "A_8") (pintype "bidirectional"))
      (node (ref "MOD3") (pin "4") (pinfunction "4_4") (pintype "bidirectional"))
      (node (ref "R14") (pin "1") (pinfunction "1_1") (pintype "passive"))
    )
    (net (code "68") (name "Net-(IC3-B)") (class "Default")
      (node (ref "IC3") (pin "7") (pinfunction "B_7") (pintype "bidirectional"))
      (node (ref "MOD3") (pin "3") (pinfunction "3_3") (pintype "bidirectional"))
      (node (ref "R14") (pin "2") (pinfunction "2_2") (pintype "passive"))
    )
    (net (code "69") (name "Net-(IC3-D)") (class "Default")
      (node (ref "IC3") (pin "3") (pinfunction "D_3") (pintype "bidirectional"))
      (node (ref "U$1") (pin "24") (pinfunction "24_24") (pintype "bidirectional"))
    )
    (net (code "70") (name "Net-(IC3-R)") (class "Default")
      (node (ref "IC3") (pin "2") (pinfunction "R_2") (pintype "bidirectional"))
      (node (ref "U$1") (pin "25") (pinfunction "25_25") (pintype "bidirectional"))
    )
    (net (code "71") (name "Net-(IC3-Y)") (class "Default")
      (node (ref "IC3") (pin "5") (pinfunction "Y_5") (pintype "bidirectional"))
      (node (ref "MOD3") (pin "1") (pinfunction "1_1") (pintype "bidirectional"))
    )
    (net (code "72") (name "Net-(IC3-Z)") (class "Default")
      (node (ref "IC3") (pin "6") (pinfunction "Z_6") (pintype "bidirectional"))
      (node (ref "MOD3") (pin "2") (pinfunction "2_2") (pintype "bidirectional"))
    )
    (net (code "73") (name "Net-(IC4-VISO)") (class "Default")
      (node (ref "C5") (pin "2") (pinfunction "2_2") (pintype "passive"))
      (node (ref "C6") (pin "2") (pinfunction "2_2") (pintype "passive"))
      (node (ref "IC4") (pin "11") (pinfunction "VSEL_11") (pintype "passive"))
      (node (ref "IC4") (pin "16") (pinfunction "VISO_16") (pintype "passive"))
    )
    (net (code "74") (name "Net-(IC4-VOA)") (class "Default")
      (node (ref "C27") (pin "2") (pinfunction "2_2") (pintype "passive"))
      (node (ref "IC4") (pin "14") (pinfunction "VOA_14") (pintype "passive"))
      (node (ref "J5") (pin "S") (pinfunction "OUT_S") (pintype "bidirectional"))
    )
    (net (code "75") (name "Net-(IC4-VOB)") (class "Default")
      (node (ref "C26") (pin "1") (pinfunction "1_1") (pintype "passive"))
      (node (ref "IC4") (pin "13") (pinfunction "VOB_13") (pintype "passive"))
      (node (ref "J4") (pin "S") (pinfunction "OUT_S") (pintype "bidirectional"))
    )
    (net (code "76") (name "Net-(IC5-VID)") (class "Default")
      (node (ref "IC5") (pin "12") (pinfunction "VID_12") (pintype "input"))
      (node (ref "R9") (pin "1") (pinfunction "1_1") (pintype "passive"))
    )
    (net (code "77") (name "Net-(IC5-VOA)") (class "Default")
      (node (ref "IC5") (pin "15") (pinfunction "VOA_15") (pintype "output"))
      (node (ref "R12") (pin "1") (pinfunction "1_1") (pintype "passive"))
    )
    (net (code "78") (name "Net-(IC5-VOB)") (class "Default")
      (node (ref "IC5") (pin "14") (pinfunction "VOB_14") (pintype "output"))
      (node (ref "R11") (pin "1") (pinfunction "1_1") (pintype "passive"))
    )
    (net (code "79") (name "Net-(IC5-VOC)") (class "Default")
      (node (ref "IC5") (pin "13") (pinfunction "VOC_13") (pintype "output"))
      (node (ref "R10") (pin "1") (pinfunction "1_1") (pintype "passive"))
    )
    (net (code "80") (name "Net-(IC6-A1)") (class "Default")
      (node (ref "IC6") (pin "1") (pinfunction "A1_1") (pintype "bidirectional"))
      (node (ref "R2") (pin "1") (pinfunction "1_1") (pintype "passive"))
    )
    (net (code "81") (name "Net-(IC6-A2)") (class "Default")
      (node (ref "IC6") (pin "3") (pinfunction "A2_3") (pintype "bidirectional"))
      (node (ref "J3") (pin "GND") (pinfunction "GND_GND") (pintype "bidirectional"))
    )
    (net (code "82") (name "Net-(IC6-C1)") (class "Default")
      (node (ref "IC6") (pin "2") (pinfunction "C1_2") (pintype "bidirectional"))
      (node (ref "J2") (pin "GND") (pinfunction "GND_GND") (pintype "bidirectional"))
    )
    (net (code "83") (name "Net-(IC6-C2)") (class "Default")
      (node (ref "IC6") (pin "4") (pinfunction "C2_4") (pintype "bidirectional"))
      (node (ref "R3") (pin "1") (pinfunction "1_1") (pintype "passive"))
    )
    (net (code "84") (name "Net-(IC7-I{slash}O0)") (class "Default")
      (node (ref "IC7") (pin "4") (pinfunction "I/O0_4") (pintype "passive"))
      (node (ref "J6") (pin "P$1") (pinfunction "P$1_P$1") (pintype "bidirectional"))
    )
    (net (code "85") (name "Net-(IC7-I{slash}O1)") (class "Default")
      (node (ref "IC7") (pin "5") (pinfunction "I/O1_5") (pintype "passive"))
      (node (ref "J6") (pin "P$3") (pinfunction "P$3_P$3") (pintype "bidirectional"))
    )
    (net (code "86") (name "Net-(IC7-I{slash}O2)") (class "Default")
      (node (ref "IC7") (pin "6") (pinfunction "I/O2_6") (pintype "passive"))
      (node (ref "J6") (pin "P$5") (pinfunction "P$5_P$5") (pintype "bidirectional"))
    )
    (net (code "87") (name "Net-(IC7-I{slash}O3)") (class "Default")
      (node (ref "IC7") (pin "7") (pinfunction "I/O3_7") (pintype "passive"))
      (node (ref "J6") (pin "P$7") (pinfunction "P$7_P$7") (pintype "bidirectional"))
    )
    (net (code "88") (name "Net-(IC9-Pad+VOUT)") (class "Default")
      (node (ref "IC9") (pin "+VOUT") (pinfunction "+VOUT_+VOUT") (pintype "bidirectional"))
      (node (ref "L1") (pin "1") (pinfunction "1_1") (pintype "passive"))
    )
    (net (code "89") (name "Net-(IC10-Pad+VOUT)") (class "Default")
      (node (ref "IC10") (pin "+VOUT") (pinfunction "+VOUT_+VOUT") (pintype "bidirectional"))
      (node (ref "L2") (pin "1") (pinfunction "1_1") (pintype "passive"))
    )
    (net (code "90") (name "Net-(IC11-Pad+VOUT)") (class "Default")
      (node (ref "IC11") (pin "+VOUT") (pinfunction "+VOUT_+VOUT") (pintype "bidirectional"))
      (node (ref "L3") (pin "1") (pinfunction "1_1") (pintype "passive"))
    )
    (net (code "91") (name "Net-(IC12-2IN)") (class "Default")
      (node (ref "IC12") (pin "5") (pinfunction "2IN_5") (pintype "bidirectional"))
      (node (ref "PORT1") (pin "1") (pinfunction "1_1") (pintype "bidirectional"))
      (node (ref "R4") (pin "1") (pinfunction "1_1") (pintype "passive"))
    )
    (net (code "92") (name "Net-(IC12-3IN)") (class "Default")
      (node (ref "IC12") (pin "7") (pinfunction "3IN_7") (pintype "bidirectional"))
      (node (ref "PORT2") (pin "1") (pinfunction "1_1") (pintype "bidirectional"))
      (node (ref "R5") (pin "1") (pinfunction "1_1") (pintype "passive"))
    )
    (net (code "93") (name "Net-(IC12-4IN)") (class "Default")
      (node (ref "IC12") (pin "9") (pinfunction "4IN_9") (pintype "bidirectional"))
      (node (ref "PORT3") (pin "1") (pinfunction "1_1") (pintype "bidirectional"))
      (node (ref "R6") (pin "2") (pinfunction "2_2") (pintype "passive"))
    )
    (net (code "94") (name "Net-(IC12-5IN)") (class "Default")
      (node (ref "IC12") (pin "11") (pinfunction "5IN_11") (pintype "bidirectional"))
      (node (ref "PORT4") (pin "1") (pinfunction "1_1") (pintype "bidirectional"))
      (node (ref "R7") (pin "2") (pinfunction "2_2") (pintype "passive"))
    )
    (net (code "95") (name "Net-(IC12-6IN)") (class "Default")
      (node (ref "IC12") (pin "14") (pinfunction "6IN_14") (pintype "bidirectional"))
      (node (ref "PORT5") (pin "1") (pinfunction "1_1") (pintype "bidirectional"))
      (node (ref "R8") (pin "2") (pinfunction "2_2") (pintype "passive"))
    )
    (net (code "96") (name "Net-(IC14-Pad+VOUT)") (class "Default")
      (node (ref "IC14") (pin "+VOUT") (pinfunction "+VOUT_+VOUT") (pintype "bidirectional"))
      (node (ref "L4") (pin "1") (pinfunction "1_1") (pintype "passive"))
    )
    (net (code "97") (name "Net-(J2-OUT)") (class "Default")
      (node (ref "J2") (pin "S") (pinfunction "OUT_S") (pintype "bidirectional"))
      (node (ref "R2") (pin "2") (pinfunction "2_2") (pintype "passive"))
    )
    (net (code "98") (name "Net-(J3-OUT)") (class "Default")
      (node (ref "J3") (pin "S") (pinfunction "OUT_S") (pintype "bidirectional"))
      (node (ref "R3") (pin "2") (pinfunction "2_2") (pintype "passive"))
    )
    (net (code "99") (name "Net-(U$8-2)") (class "Default")
      (node (ref "R1") (pin "2") (pinfunction "2_2") (pintype "passive"))
      (node (ref "U$8") (pin "P$2") (pinfunction "2_P$2") (pintype "bidirectional"))
    )
    (net (code "100") (name "VCC") (class "Default")
      (node (ref "C1") (pin "1") (pinfunction "1_1") (pintype "passive"))
      (node (ref "C11") (pin "1") (pinfunction "1_1") (pintype "passive"))
      (node (ref "C12") (pin "2") (pinfunction "2_2") (pintype "passive"))
      (node (ref "C13") (pin "1") (pinfunction "1_1") (pintype "passive"))
      (node (ref "C16") (pin "1") (pinfunction "1_1") (pintype "passive"))
      (node (ref "C2") (pin "1") (pinfunction "1_1") (pintype "passive"))
      (node (ref "C3") (pin "1") (pinfunction "1_1") (pintype "passive"))
      (node (ref "IC1") (pin "1") (pinfunction "VCC_1") (pintype "bidirectional"))
      (node (ref "IC12") (pin "1") (pinfunction "VCC_1") (pintype "bidirectional"))
      (node (ref "IC2") (pin "1") (pinfunction "VCC_1") (pintype "bidirectional"))
      (node (ref "IC3") (pin "1") (pinfunction "VCC_1") (pintype "bidirectional"))
      (node (ref "IC5") (pin "1") (pinfunction "VDD1_1") (pintype "power_in"))
      (node (ref "IC6") (pin "8") (pinfunction "CL1_8") (pintype "bidirectional"))
      (node (ref "IC8") (pin "P$2") (pinfunction "P$2_P$2") (pintype "bidirectional"))
      (node (ref "IC8") (pin "P$3") (pinfunction "P$3_P$3") (pintype "bidirectional"))
      (node (ref "U$1") (pin "3.3V") (pinfunction "3.3V_3.3V") (pintype "power_in"))
      (node (ref "U$1") (pin "3.3V3") (pinfunction "3.3V_3.3V3") (pintype "power_in"))
    )
    (net (code "101") (name "unconnected-(IC4-NC-Pad12)") (class "Default")
      (node (ref "IC4") (pin "12") (pinfunction "NC_12") (pintype "passive"))
    )
    (net (code "102") (name "unconnected-(IC4-NC_2-Pad7)") (class "Default")
      (node (ref "IC4") (pin "7") (pinfunction "NC_2_7") (pintype "passive"))
    )
    (net (code "103") (name "unconnected-(IC4-RCSEL-Pad6)") (class "Default")
      (node (ref "IC4") (pin "6") (pinfunction "RCSEL_6") (pintype "passive"))
    )
    (net (code "104") (name "unconnected-(IC4-VE2-Pad10)") (class "Default")
      (node (ref "IC4") (pin "10") (pinfunction "VE2_10") (pintype "passive"))
    )
    (net (code "105") (name "unconnected-(IC5-NIC-Pad10)") (class "Default")
      (node (ref "IC5") (pin "10") (pinfunction "NIC_10") (pintype "no_connect"))
    )
    (net (code "106") (name "unconnected-(IC5-NIC_2-Pad7)") (class "Default")
      (node (ref "IC5") (pin "7") (pinfunction "NIC_2_7") (pintype "no_connect"))
    )
    (net (code "107") (name "unconnected-(IC7-I{slash}O4-Pad10)") (class "Default")
      (node (ref "IC7") (pin "10") (pinfunction "I/O4_10") (pintype "passive"))
    )
    (net (code "108") (name "unconnected-(IC7-I{slash}O5-Pad11)") (class "Default")
      (node (ref "IC7") (pin "11") (pinfunction "I/O5_11") (pintype "passive"))
    )
    (net (code "109") (name "unconnected-(IC7-I{slash}O6-Pad12)") (class "Default")
      (node (ref "IC7") (pin "12") (pinfunction "I/O6_12") (pintype "passive"))
    )
    (net (code "110") (name "unconnected-(IC8-PadP$1)") (class "Default")
      (node (ref "IC8") (pin "P$1") (pinfunction "P$1_P$1") (pintype "bidirectional"))
    )
    (net (code "111") (name "unconnected-(IC8-PadP$7)") (class "Default")
      (node (ref "IC8") (pin "P$7") (pinfunction "P$7_P$7") (pintype "bidirectional"))
    )
    (net (code "112") (name "unconnected-(IC8-PadP$9)") (class "Default")
      (node (ref "IC8") (pin "P$9") (pinfunction "P$9_P$9") (pintype "bidirectional"))
    )
    (net (code "113") (name "unconnected-(IC8-PadP$11)") (class "Default")
      (node (ref "IC8") (pin "P$11") (pinfunction "P$11_P$11") (pintype "bidirectional"))
    )
    (net (code "114") (name "unconnected-(IC8-PadP$14)") (class "Default")
      (node (ref "IC8") (pin "P$14") (pinfunction "P$14_P$14") (pintype "bidirectional"))
    )
    (net (code "115") (name "unconnected-(IC8-PadP$16)") (class "Default")
      (node (ref "IC8") (pin "P$16") (pinfunction "P$16_P$16") (pintype "bidirectional"))
    )
    (net (code "116") (name "unconnected-(IC8-PadP$17)") (class "Default")
      (node (ref "IC8") (pin "P$17") (pinfunction "P$17_P$17") (pintype "bidirectional"))
    )
    (net (code "117") (name "unconnected-(IC8-PadP$18)") (class "Default")
      (node (ref "IC8") (pin "P$18") (pinfunction "P$18_P$18") (pintype "bidirectional"))
    )
    (net (code "118") (name "unconnected-(IC8-PadP$20)") (class "Default")
      (node (ref "IC8") (pin "P$20") (pinfunction "P$20_P$20") (pintype "bidirectional"))
    )
    (net (code "119") (name "unconnected-(IC8-PadP$25)") (class "Default")
      (node (ref "IC8") (pin "P$25") (pinfunction "P$25_P$25") (pintype "bidirectional"))
    )
    (net (code "120") (name "unconnected-(IC8-PadP$26)") (class "Default")
      (node (ref "IC8") (pin "P$26") (pinfunction "P$26_P$26") (pintype "bidirectional"))
    )
    (net (code "121") (name "unconnected-(IC8-PadP$29)") (class "Default")
      (node (ref "IC8") (pin "P$29") (pinfunction "P$29_P$29") (pintype "bidirectional"))
    )
    (net (code "122") (name "unconnected-(IC8-PadP$30)") (class "Default")
      (node (ref "IC8") (pin "P$30") (pinfunction "P$30_P$30") (pintype "bidirectional"))
    )
    (net (code "123") (name "unconnected-(IC8-PadP$33)") (class "Default")
      (node (ref "IC8") (pin "P$33") (pinfunction "P$33_P$33") (pintype "bidirectional"))
    )
    (net (code "124") (name "unconnected-(IC8-PadP$34)") (class "Default")
      (node (ref "IC8") (pin "P$34") (pinfunction "P$34_P$34") (pintype "bidirectional"))
    )
    (net (code "125") (name "unconnected-(IC9-PadNC)") (class "Default")
      (node (ref "IC9") (pin "NC") (pinfunction "NC_NC") (pintype "bidirectional"))
    )
    (net (code "126") (name "unconnected-(IC10-PadNC)") (class "Default")
      (node (ref "IC10") (pin "NC") (pinfunction "NC_NC") (pintype "bidirectional"))
    )
    (net (code "127") (name "unconnected-(IC11-PadNC)") (class "Default")
      (node (ref "IC11") (pin "NC") (pinfunction "NC_NC") (pintype "bidirectional"))
    )
    (net (code "128") (name "unconnected-(IC12-1IN-Pad3)") (class "Default")
      (node (ref "IC12") (pin "3") (pinfunction "1IN_3") (pintype "bidirectional"))
    )
    (net (code "129") (name "unconnected-(IC12-1OUT-Pad2)") (class "Default")
      (node (ref "IC12") (pin "2") (pinfunction "1OUT_2") (pintype "bidirectional"))
    )
    (net (code "130") (name "unconnected-(IC12-NC-Pad16)") (class "Default")
      (node (ref "IC12") (pin "16") (pinfunction "NC_16") (pintype "bidirectional"))
    )
    (net (code "131") (name "unconnected-(IC12-NC2-Pad13)") (class "Default")
      (node (ref "IC12") (pin "13") (pinfunction "NC2_13") (pintype "bidirectional"))
    )
    (net (code "132") (name "unconnected-(IC13-COMP-Pad7)") (class "Default")
      (node (ref "IC13") (pin "7") (pinfunction "COMP_7") (pintype "passive"))
    )
    (net (code "133") (name "unconnected-(IC13-NIC-Pad3)") (class "Default")
      (node (ref "IC13") (pin "3") (pinfunction "NIC_3") (pintype "no_connect"))
    )
    (net (code "134") (name "unconnected-(IC13-TP-Pad8)") (class "Default")
      (node (ref "IC13") (pin "8") (pinfunction "TP_8") (pintype "passive"))
    )
    (net (code "135") (name "unconnected-(IC13-TP_2-Pad1)") (class "Default")
      (node (ref "IC13") (pin "1") (pinfunction "TP_2_1") (pintype "passive"))
    )
    (net (code "136") (name "unconnected-(IC13-TRIM-Pad5)") (class "Default")
      (node (ref "IC13") (pin "5") (pinfunction "TRIM_5") (pintype "passive"))
    )
    (net (code "137") (name "unconnected-(IC14-PadNC)") (class "Default")
      (node (ref "IC14") (pin "NC") (pinfunction "NC_NC") (pintype "bidirectional"))
    )
    (net (code "138") (name "unconnected-(MOD1-Pad7)") (class "Default")
      (node (ref "MOD1") (pin "7") (pinfunction "7_7") (pintype "bidirectional"))
    )
    (net (code "139") (name "unconnected-(MOD1-Pad8)") (class "Default")
      (node (ref "MOD1") (pin "8") (pinfunction "8_8") (pintype "bidirectional"))
    )
    (net (code "140") (name "unconnected-(MOD2-Pad7)") (class "Default")
      (node (ref "MOD2") (pin "7") (pinfunction "7_7") (pintype "bidirectional"))
    )
    (net (code "141") (name "unconnected-(MOD2-Pad8)") (class "Default")
      (node (ref "MOD2") (pin "8") (pinfunction "8_8") (pintype "bidirectional"))
    )
    (net (code "142") (name "unconnected-(MOD3-Pad7)") (class "Default")
      (node (ref "MOD3") (pin "7") (pinfunction "7_7") (pintype "bidirectional"))
    )
    (net (code "143") (name "unconnected-(MOD3-Pad8)") (class "Default")
      (node (ref "MOD3") (pin "8") (pinfunction "8_8") (pintype "bidirectional"))
    )
    (net (code "144") (name "unconnected-(PORT1-Pad2)") (class "Default")
      (node (ref "PORT1") (pin "2") (pinfunction "2_2") (pintype "bidirectional"))
    )
    (net (code "145") (name "unconnected-(PORT1-Pad8)") (class "Default")
      (node (ref "PORT1") (pin "8") (pinfunction "8_8") (pintype "bidirectional"))
    )
    (net (code "146") (name "unconnected-(PORT2-Pad2)") (class "Default")
      (node (ref "PORT2") (pin "2") (pinfunction "2_2") (pintype "bidirectional"))
    )
    (net (code "147") (name "unconnected-(PORT2-Pad8)") (class "Default")
      (node (ref "PORT2") (pin "8") (pinfunction "8_8") (pintype "bidirectional"))
    )
    (net (code "148") (name "unconnected-(PORT3-Pad2)") (class "Default")
      (node (ref "PORT3") (pin "2") (pinfunction "2_2") (pintype "bidirectional"))
    )
    (net (code "149") (name "unconnected-(PORT3-Pad8)") (class "Default")
      (node (ref "PORT3") (pin "8") (pinfunction "8_8") (pintype "bidirectional"))
    )
    (net (code "150") (name "unconnected-(PORT4-Pad2)") (class "Default")
      (node (ref "PORT4") (pin "2") (pinfunction "2_2") (pintype "bidirectional"))
    )
    (net (code "151") (name "unconnected-(PORT4-Pad8)") (class "Default")
      (node (ref "PORT4") (pin "8") (pinfunction "8_8") (pintype "bidirectional"))
    )
    (net (code "152") (name "unconnected-(PORT5-Pad2)") (class "Default")
      (node (ref "PORT5") (pin "2") (pinfunction "2_2") (pintype "bidirectional"))
    )
    (net (code "153") (name "unconnected-(PORT5-Pad8)") (class "Default")
      (node (ref "PORT5") (pin "8") (pinfunction "8_8") (pintype "bidirectional"))
    )
    (net (code "154") (name "unconnected-(U$1-10{slash}TX2{slash}PWM-Pad10)") (class "Default")
      (node (ref "U$1") (pin "10") (pinfunction "10/TX2/PWM_10") (pintype "bidirectional"))
    )
    (net (code "155") (name "unconnected-(U$1-29{slash}T{slash}PWM-Pad29)") (class "Default")
      (node (ref "U$1") (pin "29") (pinfunction "29/T/PWM_29") (pintype "bidirectional"))
    )
    (net (code "156") (name "unconnected-(U$1-30{slash}T{slash}PWM-Pad30)") (class "Default")
      (node (ref "U$1") (pin "30") (pinfunction "30/T/PWM_30") (pintype "bidirectional"))
    )
    (net (code "157") (name "unconnected-(U$1-31{slash}A12{slash}RX4-Pad31{slash}A12)") (class "Default")
      (node (ref "U$1") (pin "31/A12") (pinfunction "31/A12/RX4_31/A12") (pintype "bidirectional"))
    )
    (net (code "158") (name "unconnected-(U$1-34{slash}A15{slash}RX5{slash}CAN1-RX-Pad34{slash}A15)") (class "Default")
      (node (ref "U$1") (pin "34/A15") (pinfunction "34/A15/RX5/CAN1-RX_34/A15") (pintype "bidirectional"))
    )
    (net (code "159") (name "unconnected-(U$1-A21{slash}DAC0-PadA21)") (class "Default")
      (node (ref "U$1") (pin "A21") (pinfunction "A21/DAC0_A21") (pintype "bidirectional"))
    )
    (net (code "160") (name "unconnected-(U$1-Pad26)") (class "Default")
      (node (ref "U$1") (pin "26") (pinfunction "26_26") (pintype "bidirectional"))
    )
  )
)
